# Mabee_6Aixs_IMU_MPU6050_V1_0.net
KiCad netlist of a schematic drawn in EAGLE
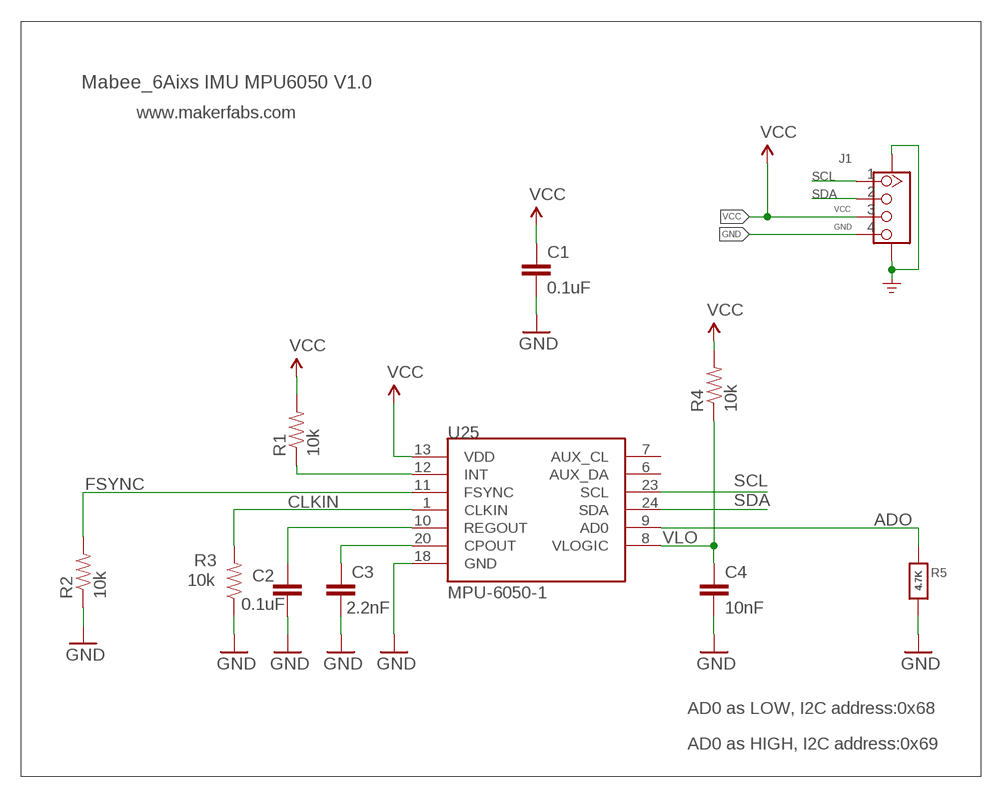
[diagram p0: schematic, sheet 1]

(export (version "E")
  (design (tool "Eeschema 10.0.6"))
  (components
    (comp (ref "C1")
      (value "0.1uF")
      (footprint "eagle-import:0603-CAP")
      (libsource (lib "eagle-import") (part "CAP0603-CAP"))
    )
    (comp (ref "C2")
      (value "0.1uF")
      (footprint "eagle-import:0603-CAP")
      (libsource (lib "eagle-import") (part "CAP0603-CAP"))
    )
    (comp (ref "C3")
      (value "2.2nF")
      (footprint "eagle-import:0603-CAP")
      (libsource (lib "eagle-import") (part "CAP0603-CAP"))
    )
    (comp (ref "C4")
      (value "10nF")
      (footprint "eagle-import:0603-CAP")
      (libsource (lib "eagle-import") (part "CAP0603-CAP"))
    )
    (comp (ref "J1")
      (value "GROVE-CONNECTOR-SMD'90D'")
      (footprint "eagle-import:HW4-SMD-2.0-90D")
      (libsource (lib "eagle-import") (part "GROVE-CONNECTOR-SMD'90D'"))
    )
    (comp (ref "R1")
      (value "10k")
      (footprint "eagle-import:0603-RES")
      (libsource (lib "eagle-import") (part "RESISTOR0603-RES"))
    )
    (comp (ref "R2")
      (value "10k")
      (footprint "eagle-import:0603-RES")
      (libsource (lib "eagle-import") (part "RESISTOR0603-RES"))
    )
    (comp (ref "R3")
      (value "10k")
      (footprint "eagle-import:0603-RES")
      (libsource (lib "eagle-import") (part "RESISTOR0603-RES"))
    )
    (comp (ref "R4")
      (value "10k")
      (footprint "eagle-import:0603-RES")
      (libsource (lib "eagle-import") (part "RESISTOR0603-RES"))
    )
    (comp (ref "R5")
      (value "4.7K")
      (footprint "eagle-import:0603-NO")
      (libsource (lib "eagle-import") (part "RESISTOR_0603_NOOUT"))
    )
    (comp (ref "U25")
      (value "MPU-6050-1")
      (footprint "eagle-import:QFN-24-4MM2")
      (libsource (lib "eagle-import") (part "MPU-6050-1"))
    )
  )
  (nets
    (net (code "1") (name "/ADO") (class "Default")
      (node (ref "R5") (pin "1") (pinfunction "1_1") (pintype "passive"))
      (node (ref "U25") (pin "9") (pinfunction "AD0_9") (pintype "bidirectional"))
    )
    (net (code "2") (name "/CLKIN") (class "Default")
      (node (ref "R3") (pin "2") (pinfunction "2_2") (pintype "passive"))
      (node (ref "U25") (pin "1") (pinfunction "CLKIN_1") (pintype "bidirectional"))
    )
    (net (code "3") (name "/FSYNC") (class "Default")
      (node (ref "R2") (pin "2") (pinfunction "2_2") (pintype "passive"))
      (node (ref "U25") (pin "11") (pinfunction "FSYNC_11") (pintype "bidirectional"))
    )
    (net (code "4") (name "/SCL") (class "Default")
      (node (ref "J1") (pin "1") (pinfunction "1_1") (pintype "bidirectional"))
      (node (ref "U25") (pin "23") (pinfunction "SCL_23") (pintype "bidirectional"))
    )
    (net (code "5") (name "/SDA") (class "Default")
      (node (ref "J1") (pin "2") (pinfunction "2_2") (pintype "bidirectional"))
      (node (ref "U25") (pin "24") (pinfunction "SDA_24") (pintype "bidirectional"))
    )
    (net (code "6") (name "/VLO") (class "Default")
      (node (ref "C4") (pin "1") (pinfunction "1_1") (pintype "passive"))
      (node (ref "R4") (pin "1") (pinfunction "1_1") (pintype "passive"))
      (node (ref "U25") (pin "8") (pinfunction "VLOGIC_8") (pintype "bidirectional"))
    )
    (net (code "7") (name "GND") (class "Default")
      (node (ref "C1") (pin "2") (pinfunction "2_2") (pintype "passive"))
      (node (ref "C2") (pin "2") (pinfunction "2_2") (pintype "passive"))
      (node (ref "C3") (pin "2") (pinfunction "2_2") (pintype "passive"))
      (node (ref "C4") (pin "2") (pinfunction "2_2") (pintype "passive"))
      (node (ref "J1") (pin "4") (pinfunction "4_4") (pintype "bidirectional"))
      (node (ref "J1") (pin "SS1") (pinfunction "SS1_SS1") (pintype "bidirectional"))
      (node (ref "J1") (pin "SS2") (pinfunction "SS2_SS2") (pintype "bidirectional"))
      (node (ref "R2") (pin "1") (pinfunction "1_1") (pintype "passive"))
      (node (ref "R3") (pin "1") (pinfunction "1_1") (pintype "passive"))
      (node (ref "R5") (pin "2") (pinfunction "2_2") (pintype "passive"))
      (node (ref "U25") (pin "18") (pinfunction "GND_18") (pintype "bidirectional"))
    )
    (net (code "8") (name "Net-(U25-CPOUT)") (class "Default")
      (node (ref "C3") (pin "1") (pinfunction "1_1") (pintype "passive"))
      (node (ref "U25") (pin "20") (pinfunction "CPOUT_20") (pintype "bidirectional"))
    )
    (net (code "9") (name "Net-(U25-INT)") (class "Default")
      (node (ref "R1") (pin "1") (pinfunction "1_1") (pintype "passive"))
      (node (ref "U25") (pin "12") (pinfunction "INT_12") (pintype "bidirectional"))
    )
    (net (code "10") (name "Net-(U25-REGOUT)") (class "Default")
      (node (ref "C2") (pin "1") (pinfunction "1_1") (pintype "passive"))
      (node (ref "U25") (pin "10") (pinfunction "REGOUT_10") (pintype "bidirectional"))
    )
    (net (code "11") (name "VCC") (class "Default")
      (node (ref "C1") (pin "1") (pinfunction "1_1") (pintype "passive"))
      (node (ref "J1") (pin "3") (pinfunction "3_3") (pintype "bidirectional"))
      (node (ref "R1") (pin "2") (pinfunction "2_2") (pintype "passive"))
      (node (ref "R4") (pin "2") (pinfunction "2_2") (pintype "passive"))
      (node (ref "U25") (pin "13") (pinfunction "VDD_13") (pintype "bidirectional"))
    )
    (net (code "12") (name "unconnected-(U25-AUX_CL-Pad7)") (class "Default")
      (node (ref "U25") (pin "7") (pinfunction "AUX_CL_7") (pintype "bidirectional"))
    )
    (net (code "13") (name "unconnected-(U25-AUX_DA-Pad6)") (class "Default")
      (node (ref "U25") (pin "6") (pinfunction "AUX_DA_6") (pintype "bidirectional"))
    )
  )
)
